# regulation.net
KiCad netlist of a schematic drawn in Altium Designer
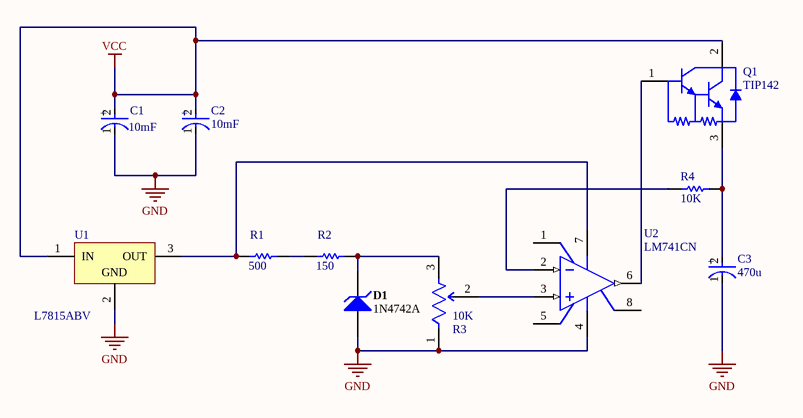
[diagram p0: regulation.SchDoc]

(export (version "E")
  (design (tool "Eeschema 10.0.6"))
  (components
    (comp (ref "C1")
      (value "10mF")
      (footprint "FP-RAD-TH-D_12_5_0_5-L_20-MFG")
      (description "Aluminum Electrolytic Capacitors (Radial Lead Type) 1000uF ±20% 25V")
      (fields (field (name "TOLERANCE") "20%") (field (name "VOLTAGE") "25V"))
      (libsource (lib "Altium Content Vault") (part "a00bbbee19879c290e62620ae7e47b1"))
    )
    (comp (ref "C2")
      (value "10mF")
      (footprint "FP-RAD-TH-D_12_5_0_5-L_20-MFG")
      (description "Aluminum Electrolytic Capacitors (Radial Lead Type) 1000uF ±20% 25V")
      (fields (field (name "TOLERANCE") "20%") (field (name "VOLTAGE") "25V"))
      (libsource (lib "Altium Content Vault") (part "a00bbbee19879c290e62620ae7e47b1"))
    )
    (comp (ref "C3")
      (value "470u")
      (footprint "FP-RAD-TH-D_16_0_5-L_15_1-MFG")
      (description "Aluminum Electrolytic Capacitors (Radial Lead Type) AEC-Q200 Qualified 330uF ±20% 50V")
      (fields (field (name "TOLERANCE") "20%"))
      (libsource (lib "Altium Content Vault") (part "a00bbbee19879c290e62620ae7e47b1"))
    )
    (comp (ref "D1")
      (value "1N4742A")
      (footprint "FAIR-DO-41-2_V")
      (description "Zener Diode, 12V, 1W, 5%, -65 to 200 degC, 2-Pin DO-41, Body 2.72 x 5.2 mm, RoHS")
      (fields (field (name "TOLERANCE") "5%") (field (name "MANUFACTURER") "Fairchild Semiconductor"))
      (libsource (lib "Altium Content Vault") (part "FAIR-DZEN-A1K2-2"))
    )
    (comp (ref "Q1")
      (value "TIP142")
      (footprint "ONSC-SOT-93_TO-218-3-340D-02")
      (description "Darlington Complementary Silicon Power Transistor, 3-Pin SOT-93, Tube")
      (fields (field (name "MANUFACTURER") "On Semiconductor"))
      (libsource (lib "Altium Content Vault") (part "ONSC-DT-NPN-B1C2E3-3_A"))
    )
    (comp (ref "R1")
      (value "500")
      (footprint "RESA60-630X240")
      (description "Axial Resistor, 1 KOhm, +/- 1%, 250 mW, -55 to 155 degC, 2-Pin THD, RoHS, Bulk")
      (fields (field (name "TOLERANCE") "1%"))
      (libsource (lib "Altium Content Vault") (part "RES-2"))
    )
    (comp (ref "R2")
      (value "150")
      (footprint "RESA60-630X240")
      (description "Axial Resistor, 1 KOhm, +/- 1%, 250 mW, -55 to 155 degC, 2-Pin THD, RoHS, Bulk")
      (fields (field (name "TOLERANCE") "1%"))
      (libsource (lib "Altium Content Vault") (part "RES-2"))
    )
    (comp (ref "R3")
      (value "10K")
      (footprint "FP-3223W-1-104-MFG")
      (description "TRIMMER 100K OHM 0.125W J LEAD")
      (fields (field (name "TOLERANCE") "20%"))
      (libsource (lib "Altium Content Vault") (part "2dcfd2547301a7d3209a5e99acfd772"))
    )
    (comp (ref "R4")
      (value "10K")
      (footprint "RESA60-630X240")
      (description "Axial Resistor, 10 KOhm, +/- 1%, 0.25 W, -55 to 155 degC, 2-Pin THD, RoHS, Bulk")
      (fields (field (name "TOLERANCE") "1%") (field (name "MANUFACTURER") "Yageo"))
      (libsource (lib "Altium Content Vault") (part "RES-2"))
    )
    (comp (ref "U1")
      (value "L7815ABV")
      (footprint "TO220")
      (description "Positive Voltage Regulator, 15V, 3-Pin TO-220")
      (libsource (lib "Altium Content Vault") (part "PM-REG-L4940-SIL3"))
    )
    (comp (ref "U2")
      (value "LM741CN")
      (footprint "N08E")
      (description "Operational Amplifier, 8-pin MDIP")
      (fields (field (name "MANUFACTURER") "National Semiconductor"))
      (libsource (lib "Altium Content Vault") (part "AMP-OPA-LM741-8"))
    )
  )
  (nets
    (net (code "1") (name "GND") (class "Default")
      (node (ref "C1") (pin "1") (pinfunction "C_1") (pintype "passive"))
      (node (ref "C2") (pin "1") (pinfunction "C_1") (pintype "passive"))
      (node (ref "C3") (pin "1") (pinfunction "C_1") (pintype "passive"))
      (node (ref "D1") (pin "1") (pinfunction "A_1") (pintype "passive"))
      (node (ref "R3") (pin "1") (pinfunction "CCW_1") (pintype "passive"))
      (node (ref "U1") (pin "2") (pinfunction "GND_2") (pintype "power_in"))
      (node (ref "U2") (pin "4") (pinfunction "V-_4") (pintype "power_in"))
    )
    (net (code "2") (name "Net-(C3-A)") (class "Default")
      (node (ref "C3") (pin "2") (pinfunction "A_2") (pintype "passive"))
      (node (ref "Q1") (pin "3") (pinfunction "E_3") (pintype "passive"))
      (node (ref "R4") (pin "2") (pinfunction "2_2") (pintype "passive"))
    )
    (net (code "3") (name "Net-(D1-K)") (class "Default")
      (node (ref "D1") (pin "2") (pinfunction "K_2") (pintype "passive"))
      (node (ref "R2") (pin "2") (pinfunction "2_2") (pintype "passive"))
      (node (ref "R3") (pin "3") (pinfunction "CW_3") (pintype "passive"))
    )
    (net (code "4") (name "Net-(Q1-B)") (class "Default")
      (node (ref "Q1") (pin "1") (pinfunction "B_1") (pintype "passive"))
      (node (ref "U2") (pin "6") (pinfunction "OUT_6") (pintype "output"))
    )
    (net (code "5") (name "Net-(R1-Pad2)") (class "Default")
      (node (ref "R1") (pin "2") (pinfunction "2_2") (pintype "passive"))
      (node (ref "R2") (pin "1") (pinfunction "1_1") (pintype "passive"))
    )
    (net (code "6") (name "Net-(R3-WIPER)") (class "Default")
      (node (ref "R3") (pin "2") (pinfunction "WIPER_2") (pintype "passive"))
      (node (ref "U2") (pin "3") (pinfunction "IN+_3") (pintype "input"))
    )
    (net (code "7") (name "Net-(U1-OUT)") (class "Default")
      (node (ref "R1") (pin "1") (pinfunction "1_1") (pintype "passive"))
      (node (ref "U1") (pin "3") (pinfunction "OUT_3") (pintype "power_in"))
      (node (ref "U2") (pin "7") (pinfunction "V+_7") (pintype "power_in"))
    )
    (net (code "8") (name "Net-(U2-IN-)") (class "Default")
      (node (ref "R4") (pin "1") (pinfunction "1_1") (pintype "passive"))
      (node (ref "U2") (pin "2") (pinfunction "IN-_2") (pintype "input"))
    )
    (net (code "9") (name "VCC") (class "Default")
      (node (ref "C1") (pin "2") (pinfunction "A_2") (pintype "passive"))
      (node (ref "C2") (pin "2") (pinfunction "A_2") (pintype "passive"))
      (node (ref "Q1") (pin "2") (pinfunction "C_2") (pintype "passive"))
      (node (ref "U1") (pin "1") (pinfunction "IN_1") (pintype "power_in"))
    )
    (net (code "10") (name "unconnected-(U2-NC-Pad8)") (class "Default")
      (node (ref "U2") (pin "8") (pinfunction "NC_8") (pintype "passive"))
    )
    (net (code "11") (name "unconnected-(U2-OFS_NULL-Pad1)") (class "Default")
      (node (ref "U2") (pin "1") (pinfunction "OFS_NULL_1") (pintype "passive"))
    )
    (net (code "12") (name "unconnected-(U2-OFS_NULL-Pad5)") (class "Default")
      (node (ref "U2") (pin "5") (pinfunction "OFS_NULL_5") (pintype "passive"))
    )
  )
)
